# openSX70_ALADDIN_V397SEEED_20180213.net
KiCad netlist of a schematic drawn in EAGLE
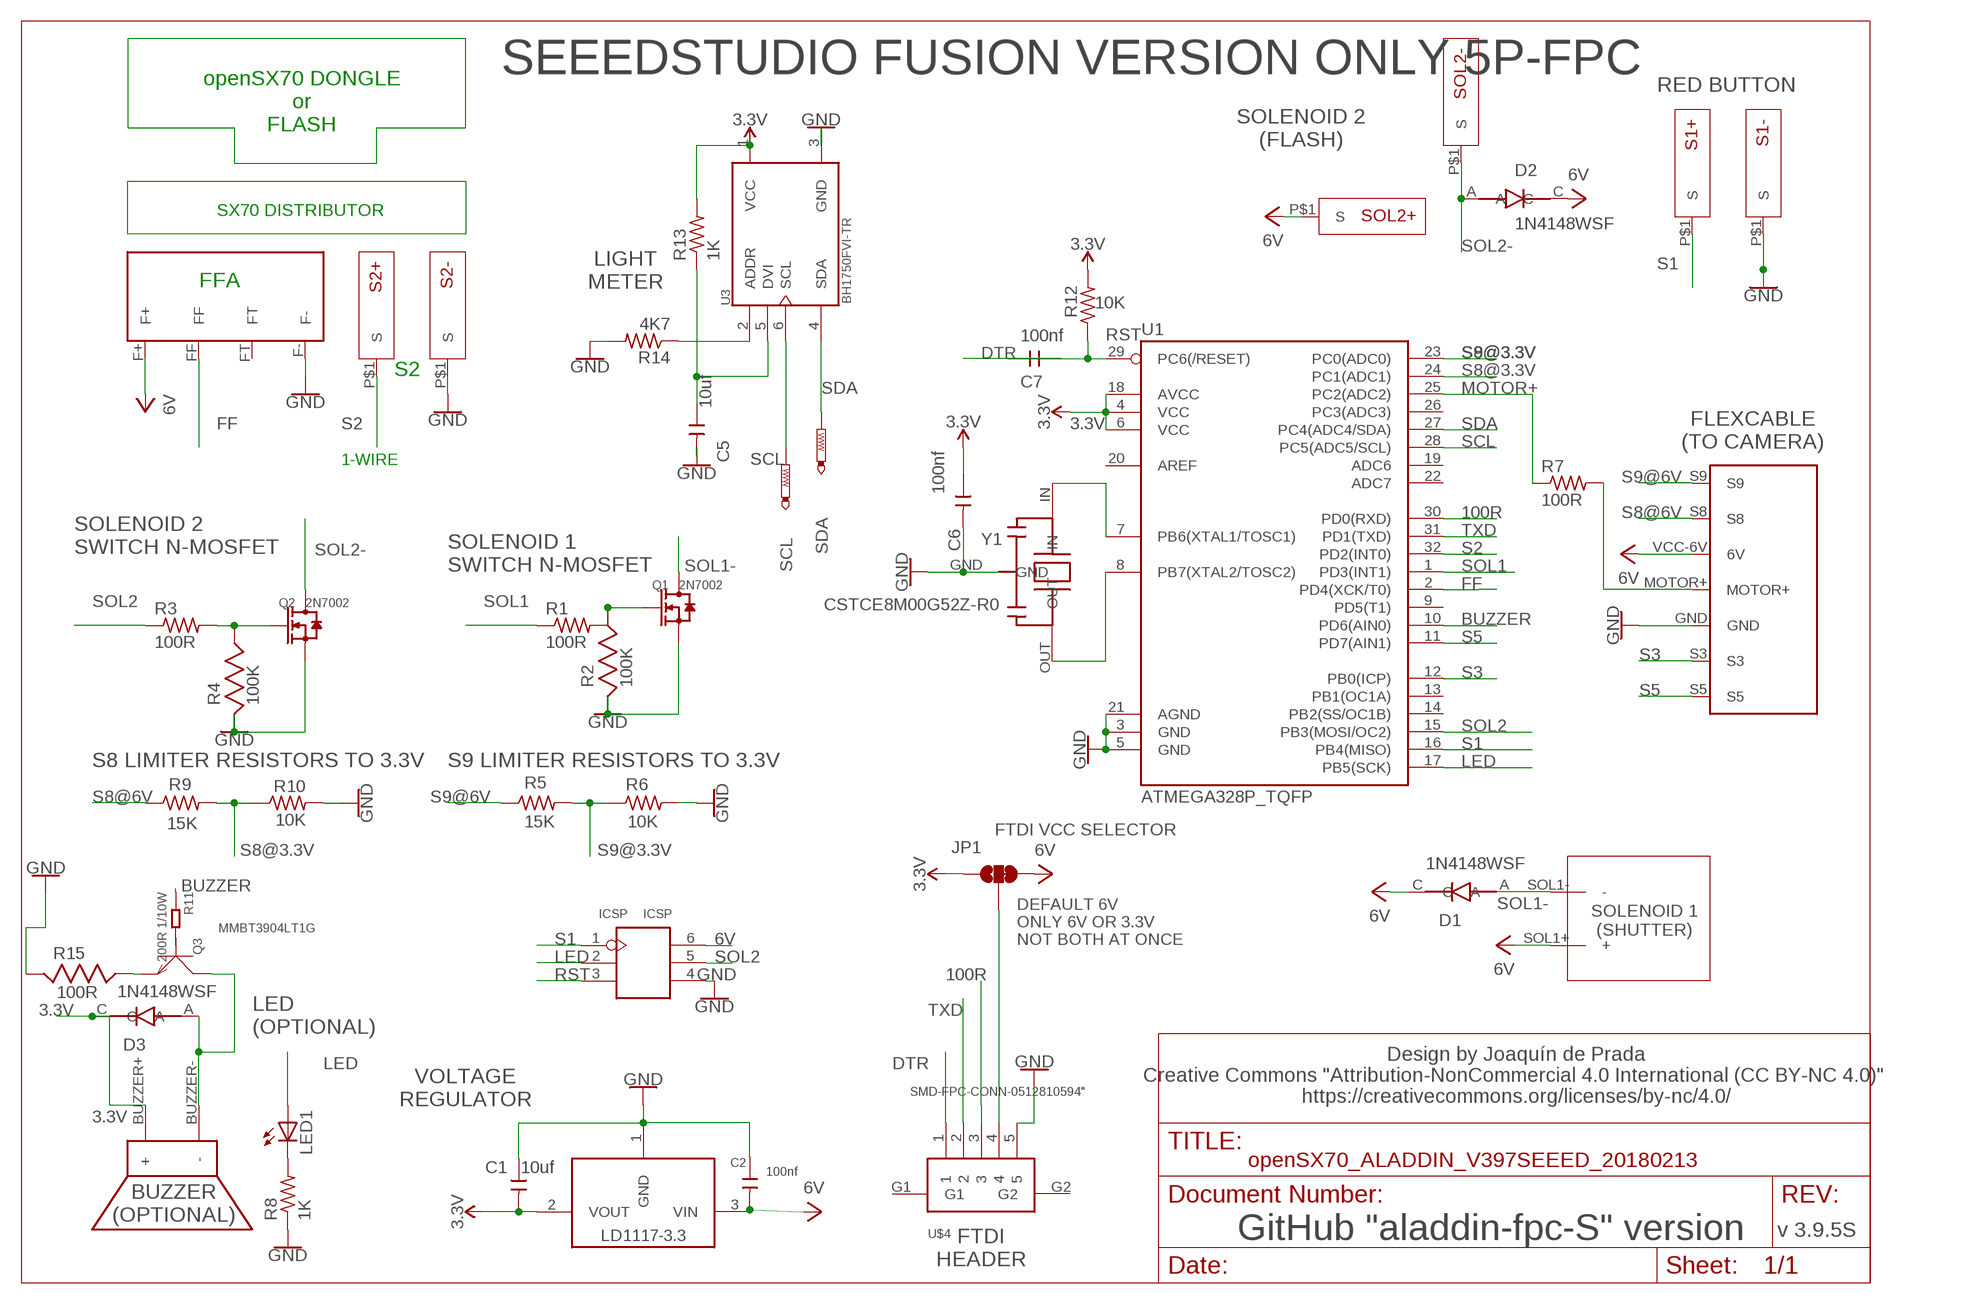
[diagram p0: schematic, sheet 1]

(export (version "E")
  (design (tool "Eeschema 10.0.6"))
  (components
    (comp (ref "C1")
      (value "10uf")
      (footprint "eagle-import:C0603")
      (fields (field (name "MPN") "CC0603KRX5R6BB106"))
      (libsource (lib "eagle-import") (part "CERAMIC-10UF-10V-10%-X5R(0603)"))
    )
    (comp (ref "C2")
      (value "100nf")
      (footprint "eagle-import:C0603")
      (fields (field (name "MPN") "CC0603KRX7R9BB104"))
      (libsource (lib "eagle-import") (part "CERAMIC-100NF-50V-10%-X7R(0603)"))
    )
    (comp (ref "C5")
      (value "10uf")
      (footprint "eagle-import:C0603")
      (fields (field (name "MPN") "CC0603KRX5R6BB106"))
      (libsource (lib "eagle-import") (part "CERAMIC-10UF-10V-10%-X5R(0603)"))
    )
    (comp (ref "C6")
      (value "100nf")
      (footprint "eagle-import:C0603")
      (fields (field (name "MPN") "CC0603KRX7R9BB104"))
      (libsource (lib "eagle-import") (part "CERAMIC-100NF-50V-10%-X7R(0603)"))
    )
    (comp (ref "C7")
      (value "100nf")
      (footprint "eagle-import:C0603")
      (fields (field (name "MPN") "CC0603KRX7R9BB104"))
      (libsource (lib "eagle-import") (part "CERAMIC-100NF-50V-10%-X7R(0603)"))
    )
    (comp (ref "D1")
      (value "1N4148WSF")
      (footprint "eagle-import:SODFL2512X100N")
      (fields (field (name "MANUFACTURER") "Fairchild Semiconductor"))
      (libsource (lib "eagle-import") (part "1N4148WS"))
    )
    (comp (ref "D2")
      (value "1N4148WSF")
      (footprint "eagle-import:SODFL2512X100N")
      (fields (field (name "MANUFACTURER") "Fairchild Semiconductor"))
      (libsource (lib "eagle-import") (part "1N4148WS"))
    )
    (comp (ref "D3")
      (value "1N4148WSF")
      (footprint "eagle-import:SODFL2512X100N")
      (fields (field (name "MANUFACTURER") "Fairchild Semiconductor"))
      (libsource (lib "eagle-import") (part "1N4148WS"))
    )
    (comp (ref "ICSP")
      (value "ICSP")
      (footprint "eagle-import:H2X3-2.54")
      (libsource (lib "eagle-import") (part "ICSP"))
    )
    (comp (ref "JP1")
      (value "FTDI VCC SELECTOR")
      (footprint "eagle-import:SMT-JUMPER_3_1-NC_TRACE_SILK")
      (libsource (lib "eagle-import") (part "JUMPER-SMT_3_1-NC_TRACE_SILK"))
    )
    (comp (ref "LD11172.5V")
      (value "LD1117 2.5V")
      (footprint "eagle-import:SOT223")
      (fields (field (name "MF") "Advanced Monolithic Systems") (field (name "MP") "AMS1117-5.0"))
      (libsource (lib "eagle-import") (part "LD1117-3.3"))
    )
    (comp (ref "LED1")
      (value "LEDCHIPLED_0805")
      (footprint "eagle-import:CHIPLED_0805")
      (libsource (lib "eagle-import") (part "LEDCHIPLED_0805"))
    )
    (comp (ref "Q1")
      (value "2N7002")
      (footprint "eagle-import:SOT-23")
      (fields (field (name "MPN") "2N7002,215"))
      (libsource (lib "eagle-import") (part "SMD-MOSFET-N-CH-60V-300MA-LOGIC-LEVEL-FET-2N7002(SOT-23)"))
    )
    (comp (ref "Q2")
      (value "2N7002")
      (footprint "eagle-import:SOT-23")
      (fields (field (name "MPN") "2N7002,215"))
      (libsource (lib "eagle-import") (part "SMD-MOSFET-N-CH-60V-300MA-LOGIC-LEVEL-FET-2N7002(SOT-23)"))
    )
    (comp (ref "Q3")
      (value "MMBT3904LT1G")
      (footprint "eagle-import:SOT-23")
      (libsource (lib "eagle-import") (part "SMD-TRANSISTORS-NPN-40V-200MA-MMBT3904LT1G(SOT-23)"))
    )
    (comp (ref "R1")
      (value "100R")
      (footprint "eagle-import:R0603")
      (libsource (lib "eagle-import") (part "R-US_R0603"))
    )
    (comp (ref "R2")
      (value "100K")
      (footprint "eagle-import:ERJ-3EKF1003V_RESC1608X55")
      (fields (field (name "MANUFACTURER") "PANASONIC"))
      (libsource (lib "eagle-import") (part "ERJ-3EKF1003V"))
    )
    (comp (ref "R3")
      (value "100R")
      (footprint "eagle-import:R0603")
      (libsource (lib "eagle-import") (part "R-US_R0603"))
    )
    (comp (ref "R4")
      (value "100K")
      (footprint "eagle-import:ERJ-3EKF1003V_RESC1608X55")
      (fields (field (name "MANUFACTURER") "PANASONIC"))
      (libsource (lib "eagle-import") (part "ERJ-3EKF1003V"))
    )
    (comp (ref "R5")
      (value "15K")
      (footprint "eagle-import:R0603")
      (libsource (lib "eagle-import") (part "R-US_R0603"))
    )
    (comp (ref "R6")
      (value "10K")
      (footprint "eagle-import:R0603")
      (libsource (lib "eagle-import") (part "R-US_R0603"))
    )
    (comp (ref "R7")
      (value "100R")
      (footprint "eagle-import:R0603")
      (libsource (lib "eagle-import") (part "R-US_R0603"))
    )
    (comp (ref "R8")
      (value "1K")
      (footprint "eagle-import:R0603")
      (libsource (lib "eagle-import") (part "R-US_R0603"))
    )
    (comp (ref "R9")
      (value "15K")
      (footprint "eagle-import:R0603")
      (libsource (lib "eagle-import") (part "R-US_R0603"))
    )
    (comp (ref "R10")
      (value "10K")
      (footprint "eagle-import:R0603")
      (libsource (lib "eagle-import") (part "R-US_R0603"))
    )
    (comp (ref "R11")
      (value "200R 1/10W")
      (footprint "eagle-import:R0603")
      (fields (field (name "MPN") "RC0603JR-07200RL"))
      (libsource (lib "eagle-import") (part "SMD-RES-200R-5%-1/10W(0603)"))
    )
    (comp (ref "R12")
      (value "10K")
      (footprint "eagle-import:R0603")
      (libsource (lib "eagle-import") (part "R-US_R0603"))
    )
    (comp (ref "R13")
      (value "1K")
      (footprint "eagle-import:R0603")
      (libsource (lib "eagle-import") (part "R-US_R0603"))
    )
    (comp (ref "R14")
      (value "4K7")
      (footprint "eagle-import:R0603")
      (libsource (lib "eagle-import") (part "R-US_R0603"))
    )
    (comp (ref "R15")
      (value "CRCW0603100RFKEA")
      (footprint "eagle-import:CRCW0603100RFKEA_RESC1608X55")
      (fields (field (name "MANUFACTURER") "VISHAY"))
      (libsource (lib "eagle-import") (part "CRCW0603100RFKEA"))
    )
    (comp (ref "S1+")
      (value "SX70-S-PAD-NEW")
      (footprint "eagle-import:SX70-S-PAD2")
      (libsource (lib "eagle-import") (part "SX70-S-PAD-NEW"))
    )
    (comp (ref "S1-")
      (value "SX70-S-PAD-NEW")
      (footprint "eagle-import:SX70-S-PAD2")
      (libsource (lib "eagle-import") (part "SX70-S-PAD-NEW"))
    )
    (comp (ref "S2+")
      (value "SX70-S-PAD-NEW")
      (footprint "eagle-import:SX70-S-PAD2")
      (libsource (lib "eagle-import") (part "SX70-S-PAD-NEW"))
    )
    (comp (ref "S2-")
      (value "SX70-S-PAD-NEW")
      (footprint "eagle-import:SX70-S-PAD2")
      (libsource (lib "eagle-import") (part "SX70-S-PAD-NEW"))
    )
    (comp (ref "SCL")
      (value "PTR1TP08R")
      (footprint "eagle-import:TP08R")
      (libsource (lib "eagle-import") (part "PTR1TP08R"))
    )
    (comp (ref "SDA")
      (value "PTR1TP08R")
      (footprint "eagle-import:TP08R")
      (libsource (lib "eagle-import") (part "PTR1TP08R"))
    )
    (comp (ref "SOL1")
      (value "SX70-SOLENOID1-2PADS")
      (footprint "eagle-import:SX70-SOLENOID1-2")
      (libsource (lib "eagle-import") (part "SX70-SOLENOID1-2PADS"))
    )
    (comp (ref "SOL2+")
      (value "SX70-S-PAD-NEW")
      (footprint "eagle-import:SX70-S-PAD2")
      (libsource (lib "eagle-import") (part "SX70-S-PAD-NEW"))
    )
    (comp (ref "SOL2-")
      (value "SX70-S-PAD-NEW")
      (footprint "eagle-import:SX70-S-PAD2")
      (libsource (lib "eagle-import") (part "SX70-S-PAD-NEW"))
    )
    (comp (ref "U$1")
      (value "SX70-7-PAD")
      (footprint "eagle-import:SX70-7-PAD")
      (libsource (lib "eagle-import") (part "SX70-7-PAD"))
    )
    (comp (ref "U$2")
      (value "FFA")
      (footprint "eagle-import:FFA-PAD-PACKAGE")
      (libsource (lib "eagle-import") (part "SX70-FFA-PAD"))
    )
    (comp (ref "U$3")
      (value "CSET8-5G_V2")
      (footprint "eagle-import:CSET8-5G_PACKAGE")
      (libsource (lib "eagle-import") (part "CSET8-5G_V2"))
    )
    (comp (ref "U$4")
      (value "SMD-FPC-CONN-0512810594\"")
      (footprint "eagle-import:51281-0594")
      (libsource (lib "eagle-import") (part "SMD-FPC-CONN-0512810594{dblquote}"))
    )
    (comp (ref "U1")
      (value "ATMEGA328P_TQFP")
      (footprint "eagle-import:TQFP32-08")
      (libsource (lib "eagle-import") (part "ATMEGA328P_TQFP"))
    )
    (comp (ref "U3")
      (value "BH1750FVI-TR")
      (footprint "eagle-import:SOTFL50P300X75-6N")
      (fields (field (name "MF") "Rohm"))
      (libsource (lib "eagle-import") (part "BH1750FVI-TR"))
    )
    (comp (ref "Y1")
      (value "CSTCE8M00G52Z-R0")
      (footprint "eagle-import:CFP95P160X100-3N")
      (fields (field (name "MF") "Murata") (field (name "MP") "CSTCE16M0V53-R0"))
      (libsource (lib "eagle-import") (part "CSTCE16M0V53-R0"))
    )
  )
  (nets
    (net (code "1") (name "/100R") (class "Default")
      (node (ref "U$4") (pin "3") (pinfunction "3_3") (pintype "bidirectional"))
      (node (ref "U1") (pin "30") (pinfunction "PD0(RXD)_30") (pintype "bidirectional"))
    )
    (net (code "2") (name "/BUZZER") (class "Default")
      (node (ref "R11") (pin "1") (pinfunction "1_1") (pintype "passive"))
      (node (ref "U1") (pin "10") (pinfunction "PD6(AIN0)_10") (pintype "bidirectional"))
    )
    (net (code "3") (name "/DTR") (class "Default")
      (node (ref "C7") (pin "1") (pinfunction "1_1") (pintype "passive"))
      (node (ref "U$4") (pin "1") (pinfunction "1_1") (pintype "bidirectional"))
    )
    (net (code "4") (name "/FF") (class "Default")
      (node (ref "U$2") (pin "FF") (pinfunction "FF_FF") (pintype "bidirectional"))
      (node (ref "U1") (pin "2") (pinfunction "PD4(XCK/T0)_2") (pintype "bidirectional"))
    )
    (net (code "5") (name "/LED") (class "Default")
      (node (ref "ICSP") (pin "2") (pinfunction "SCK_2") (pintype "bidirectional"))
      (node (ref "LED1") (pin "A") (pinfunction "A_A") (pintype "passive"))
      (node (ref "U1") (pin "17") (pinfunction "PB5(SCK)_17") (pintype "bidirectional"))
    )
    (net (code "6") (name "/MOTOR+") (class "Default")
      (node (ref "R7") (pin "1") (pinfunction "1_1") (pintype "passive"))
      (node (ref "U1") (pin "25") (pinfunction "PC2(ADC2)_25") (pintype "bidirectional"))
    )
    (net (code "7") (name "/RST") (class "Default")
      (node (ref "C7") (pin "2") (pinfunction "2_2") (pintype "passive"))
      (node (ref "ICSP") (pin "3") (pinfunction "RST_3") (pintype "bidirectional"))
      (node (ref "R12") (pin "1") (pinfunction "1_1") (pintype "passive"))
      (node (ref "U1") (pin "29") (pinfunction "PC6(/RESET)_29") (pintype "bidirectional"))
    )
    (net (code "8") (name "/S1") (class "Default")
      (node (ref "ICSP") (pin "1") (pinfunction "MISO_1") (pintype "bidirectional"))
      (node (ref "S1+") (pin "P$1") (pinfunction "S_P$1") (pintype "bidirectional"))
      (node (ref "U1") (pin "16") (pinfunction "PB4(MISO)_16") (pintype "bidirectional"))
    )
    (net (code "9") (name "/S2") (class "Default")
      (node (ref "S2+") (pin "P$1") (pinfunction "S_P$1") (pintype "bidirectional"))
      (node (ref "U1") (pin "32") (pinfunction "PD2(INT0)_32") (pintype "bidirectional"))
    )
    (net (code "10") (name "/S3") (class "Default")
      (node (ref "U$1") (pin "S3") (pinfunction "S3_S3") (pintype "bidirectional"))
      (node (ref "U1") (pin "12") (pinfunction "PB0(ICP)_12") (pintype "bidirectional"))
    )
    (net (code "11") (name "/S5") (class "Default")
      (node (ref "U$1") (pin "S5") (pinfunction "S5_S5") (pintype "bidirectional"))
      (node (ref "U1") (pin "11") (pinfunction "PD7(AIN1)_11") (pintype "bidirectional"))
    )
    (net (code "12") (name "/S8@3.3V") (class "Default")
      (node (ref "R10") (pin "1") (pinfunction "1_1") (pintype "passive"))
      (node (ref "R9") (pin "2") (pinfunction "2_2") (pintype "passive"))
      (node (ref "U1") (pin "24") (pinfunction "PC1(ADC1)_24") (pintype "bidirectional"))
    )
    (net (code "13") (name "/S8@6V") (class "Default")
      (node (ref "R9") (pin "1") (pinfunction "1_1") (pintype "passive"))
      (node (ref "U$1") (pin "S8") (pinfunction "S8_S8") (pintype "bidirectional"))
    )
    (net (code "14") (name "/S9@3.3V") (class "Default")
      (node (ref "R5") (pin "2") (pinfunction "2_2") (pintype "passive"))
      (node (ref "R6") (pin "1") (pinfunction "1_1") (pintype "passive"))
      (node (ref "U1") (pin "23") (pinfunction "PC0(ADC0)_23") (pintype "bidirectional"))
    )
    (net (code "15") (name "/S9@6V") (class "Default")
      (node (ref "R5") (pin "1") (pinfunction "1_1") (pintype "passive"))
      (node (ref "U$1") (pin "S9") (pinfunction "S9_S9") (pintype "bidirectional"))
    )
    (net (code "16") (name "/SCL") (class "Default")
      (node (ref "SCL") (pin "TP") (pinfunction "TP_TP") (pintype "input"))
      (node (ref "U1") (pin "28") (pinfunction "PC5(ADC5/SCL)_28") (pintype "bidirectional"))
      (node (ref "U3") (pin "6") (pinfunction "SCL_6") (pintype "input"))
    )
    (net (code "17") (name "/SDA") (class "Default")
      (node (ref "SDA") (pin "TP") (pinfunction "TP_TP") (pintype "input"))
      (node (ref "U1") (pin "27") (pinfunction "PC4(ADC4/SDA)_27") (pintype "bidirectional"))
      (node (ref "U3") (pin "4") (pinfunction "SDA_4") (pintype "bidirectional"))
    )
    (net (code "18") (name "/SOL1") (class "Default")
      (node (ref "R1") (pin "1") (pinfunction "1_1") (pintype "passive"))
      (node (ref "U1") (pin "1") (pinfunction "PD3(INT1)_1") (pintype "bidirectional"))
    )
    (net (code "19") (name "/SOL1-") (class "Default")
      (node (ref "D1") (pin "A") (pinfunction "A_A") (pintype "passive"))
      (node (ref "Q1") (pin "3") (pinfunction "D_3") (pintype "passive"))
      (node (ref "SOL1") (pin "SOL1-") (pinfunction "-_SOL1-") (pintype "bidirectional"))
    )
    (net (code "20") (name "/SOL2") (class "Default")
      (node (ref "ICSP") (pin "5") (pinfunction "MOSI_5") (pintype "bidirectional"))
      (node (ref "R3") (pin "1") (pinfunction "1_1") (pintype "passive"))
      (node (ref "U1") (pin "15") (pinfunction "PB3(MOSI/OC2)_15") (pintype "bidirectional"))
    )
    (net (code "21") (name "/SOL2-") (class "Default")
      (node (ref "D2") (pin "A") (pinfunction "A_A") (pintype "passive"))
      (node (ref "Q2") (pin "3") (pinfunction "D_3") (pintype "passive"))
      (node (ref "SOL2-") (pin "P$1") (pinfunction "S_P$1") (pintype "bidirectional"))
    )
    (net (code "22") (name "/TXD") (class "Default")
      (node (ref "U$4") (pin "2") (pinfunction "2_2") (pintype "bidirectional"))
      (node (ref "U1") (pin "31") (pinfunction "PD1(TXD)_31") (pintype "bidirectional"))
    )
    (net (code "23") (name "3.3V") (class "Default")
      (node (ref "C1") (pin "2") (pinfunction "2_2") (pintype "passive"))
      (node (ref "C6") (pin "1") (pinfunction "1_1") (pintype "passive"))
      (node (ref "D3") (pin "C") (pinfunction "C_C") (pintype "passive"))
      (node (ref "JP1") (pin "1") (pinfunction "1_1") (pintype "passive"))
      (node (ref "LD11172.5V") (pin "2") (pinfunction "VOUT_2") (pintype "bidirectional"))
      (node (ref "R12") (pin "2") (pinfunction "2_2") (pintype "passive"))
      (node (ref "R13") (pin "2") (pinfunction "2_2") (pintype "passive"))
      (node (ref "U$3") (pin "BUZZER+") (pinfunction "+_BUZZER+") (pintype "bidirectional"))
      (node (ref "U1") (pin "18") (pinfunction "AVCC_18") (pintype "bidirectional"))
      (node (ref "U1") (pin "4") (pinfunction "VCC_4") (pintype "bidirectional"))
      (node (ref "U1") (pin "6") (pinfunction "VCC_6") (pintype "bidirectional"))
      (node (ref "U3") (pin "1") (pinfunction "VCC_1") (pintype "power_in"))
    )
    (net (code "24") (name "6V") (class "Default")
      (node (ref "C2") (pin "2") (pinfunction "2_2") (pintype "passive"))
      (node (ref "D1") (pin "C") (pinfunction "C_C") (pintype "passive"))
      (node (ref "D2") (pin "C") (pinfunction "C_C") (pintype "passive"))
      (node (ref "ICSP") (pin "6") (pinfunction "VCC_6") (pintype "bidirectional"))
      (node (ref "JP1") (pin "3") (pinfunction "3_3") (pintype "passive"))
      (node (ref "LD11172.5V") (pin "3") (pinfunction "VIN_3") (pintype "bidirectional"))
      (node (ref "SOL1") (pin "SOL1+") (pinfunction "+_SOL1+") (pintype "bidirectional"))
      (node (ref "SOL2+") (pin "P$1") (pinfunction "S_P$1") (pintype "bidirectional"))
      (node (ref "U$1") (pin "VCC-6V") (pinfunction "6V_VCC-6V") (pintype "bidirectional"))
      (node (ref "U$2") (pin "F+") (pinfunction "F+_F+") (pintype "bidirectional"))
    )
    (net (code "25") (name "GND") (class "Default")
      (node (ref "C1") (pin "1") (pinfunction "1_1") (pintype "passive"))
      (node (ref "C2") (pin "1") (pinfunction "1_1") (pintype "passive"))
      (node (ref "C5") (pin "2") (pinfunction "2_2") (pintype "passive"))
      (node (ref "C6") (pin "2") (pinfunction "2_2") (pintype "passive"))
      (node (ref "ICSP") (pin "4") (pinfunction "GND_4") (pintype "bidirectional"))
      (node (ref "LD11172.5V") (pin "1") (pinfunction "GND_1") (pintype "bidirectional"))
      (node (ref "Q1") (pin "2") (pinfunction "S_2") (pintype "passive"))
      (node (ref "Q2") (pin "2") (pinfunction "S_2") (pintype "passive"))
      (node (ref "R10") (pin "2") (pinfunction "2_2") (pintype "passive"))
      (node (ref "R14") (pin "2") (pinfunction "2_2") (pintype "passive"))
      (node (ref "R15") (pin "1") (pinfunction "1_1") (pintype "passive"))
      (node (ref "R2") (pin "1") (pinfunction "1_1") (pintype "passive"))
      (node (ref "R4") (pin "1") (pinfunction "1_1") (pintype "passive"))
      (node (ref "R6") (pin "2") (pinfunction "2_2") (pintype "passive"))
      (node (ref "R8") (pin "1") (pinfunction "1_1") (pintype "passive"))
      (node (ref "S1-") (pin "P$1") (pinfunction "S_P$1") (pintype "bidirectional"))
      (node (ref "S2-") (pin "P$1") (pinfunction "S_P$1") (pintype "bidirectional"))
      (node (ref "U$1") (pin "GND") (pinfunction "GND_GND") (pintype "bidirectional"))
      (node (ref "U$2") (pin "F-") (pinfunction "F-_F-") (pintype "bidirectional"))
      (node (ref "U$4") (pin "5") (pinfunction "5_5") (pintype "bidirectional"))
      (node (ref "U1") (pin "21") (pinfunction "AGND_21") (pintype "bidirectional"))
      (node (ref "U1") (pin "3") (pinfunction "GND_3") (pintype "bidirectional"))
      (node (ref "U1") (pin "5") (pinfunction "GND_5") (pintype "bidirectional"))
      (node (ref "U3") (pin "3") (pinfunction "GND_3") (pintype "power_in"))
      (node (ref "Y1") (pin "GND") (pinfunction "GND_GND") (pintype "passive"))
    )
    (net (code "26") (name "Net-(JP1-Pad2)") (class "Default")
      (node (ref "JP1") (pin "2") (pinfunction "2_2") (pintype "passive"))
      (node (ref "U$4") (pin "4") (pinfunction "4_4") (pintype "bidirectional"))
    )
    (net (code "27") (name "Net-(LED1-PadC)") (class "Default")
      (node (ref "LED1") (pin "C") (pinfunction "C_C") (pintype "passive"))
      (node (ref "R8") (pin "2") (pinfunction "2_2") (pintype "passive"))
    )
    (net (code "28") (name "Net-(Q1-G)") (class "Default")
      (node (ref "Q1") (pin "1") (pinfunction "G_1") (pintype "passive"))
      (node (ref "R1") (pin "2") (pinfunction "2_2") (pintype "passive"))
      (node (ref "R2") (pin "2") (pinfunction "2_2") (pintype "passive"))
    )
    (net (code "29") (name "Net-(Q2-G)") (class "Default")
      (node (ref "Q2") (pin "1") (pinfunction "G_1") (pintype "passive"))
      (node (ref "R3") (pin "2") (pinfunction "2_2") (pintype "passive"))
      (node (ref "R4") (pin "2") (pinfunction "2_2") (pintype "passive"))
    )
    (net (code "30") (name "Net-(Q3-B)") (class "Default")
      (node (ref "Q3") (pin "1") (pinfunction "B_1") (pintype "passive"))
      (node (ref "R11") (pin "2") (pinfunction "2_2") (pintype "passive"))
    )
    (net (code "31") (name "Net-(Q3-C)") (class "Default")
      (node (ref "D3") (pin "A") (pinfunction "A_A") (pintype "passive"))
      (node (ref "Q3") (pin "3") (pinfunction "C_3") (pintype "passive"))
      (node (ref "U$3") (pin "BUZZER-") (pinfunction "-_BUZZER-") (pintype "bidirectional"))
    )
    (net (code "32") (name "Net-(Q3-E)") (class "Default")
      (node (ref "Q3") (pin "2") (pinfunction "E_2") (pintype "passive"))
      (node (ref "R15") (pin "2") (pinfunction "2_2") (pintype "passive"))
    )
    (net (code "33") (name "Net-(R7-Pad2)") (class "Default")
      (node (ref "R7") (pin "2") (pinfunction "2_2") (pintype "passive"))
      (node (ref "U$1") (pin "MOTOR+") (pinfunction "MOTOR+_MOTOR+") (pintype "bidirectional"))
    )
    (net (code "34") (name "Net-(U1-PB6(XTAL1{slash}TOSC1))") (class "Default")
      (node (ref "U1") (pin "7") (pinfunction "PB6(XTAL1/TOSC1)_7") (pintype "bidirectional"))
      (node (ref "Y1") (pin "IN") (pinfunction "IN_IN") (pintype "input"))
    )
    (net (code "35") (name "Net-(U1-PB7(XTAL2{slash}TOSC2))") (class "Default")
      (node (ref "U1") (pin "8") (pinfunction "PB7(XTAL2/TOSC2)_8") (pintype "bidirectional"))
      (node (ref "Y1") (pin "OUT") (pinfunction "OUT_OUT") (pintype "output"))
    )
    (net (code "36") (name "Net-(U3-ADDR)") (class "Default")
      (node (ref "R14") (pin "1") (pinfunction "1_1") (pintype "passive"))
      (node (ref "U3") (pin "2") (pinfunction "ADDR_2") (pintype "input"))
    )
    (net (code "37") (name "Net-(U3-DVI)") (class "Default")
      (node (ref "C5") (pin "1") (pinfunction "1_1") (pintype "passive"))
      (node (ref "R13") (pin "1") (pinfunction "1_1") (pintype "passive"))
      (node (ref "U3") (pin "5") (pinfunction "DVI_5") (pintype "input"))
    )
    (net (code "38") (name "unconnected-(U$2-PadFT)") (class "Default")
      (node (ref "U$2") (pin "FT") (pinfunction "FT_FT") (pintype "bidirectional"))
    )
    (net (code "39") (name "unconnected-(U$4-PadG1)") (class "Default")
      (node (ref "U$4") (pin "G1") (pinfunction "G1_G1") (pintype "bidirectional"))
    )
    (net (code "40") (name "unconnected-(U$4-PadG2)") (class "Default")
      (node (ref "U$4") (pin "G2") (pinfunction "G2_G2") (pintype "bidirectional"))
    )
    (net (code "41") (name "unconnected-(U1-ADC6-Pad19)") (class "Default")
      (node (ref "U1") (pin "19") (pinfunction "ADC6_19") (pintype "bidirectional"))
    )
    (net (code "42") (name "unconnected-(U1-ADC7-Pad22)") (class "Default")
      (node (ref "U1") (pin "22") (pinfunction "ADC7_22") (pintype "bidirectional"))
    )
    (net (code "43") (name "unconnected-(U1-AREF-Pad20)") (class "Default")
      (node (ref "U1") (pin "20") (pinfunction "AREF_20") (pintype "bidirectional"))
    )
    (net (code "44") (name "unconnected-(U1-PB1(OC1A)-Pad13)") (class "Default")
      (node (ref "U1") (pin "13") (pinfunction "PB1(OC1A)_13") (pintype "bidirectional"))
    )
    (net (code "45") (name "unconnected-(U1-PB2(SS{slash}OC1B)-Pad14)") (class "Default")
      (node (ref "U1") (pin "14") (pinfunction "PB2(SS/OC1B)_14") (pintype "bidirectional"))
    )
    (net (code "46") (name "unconnected-(U1-PC3(ADC3)-Pad26)") (class "Default")
      (node (ref "U1") (pin "26") (pinfunction "PC3(ADC3)_26") (pintype "bidirectional"))
    )
    (net (code "47") (name "unconnected-(U1-PD5(T1)-Pad9)") (class "Default")
      (node (ref "U1") (pin "9") (pinfunction "PD5(T1)_9") (pintype "bidirectional"))
    )
  )
)
